# pcb_aux_sensors.net
KiCad netlist of a schematic drawn in EAGLE
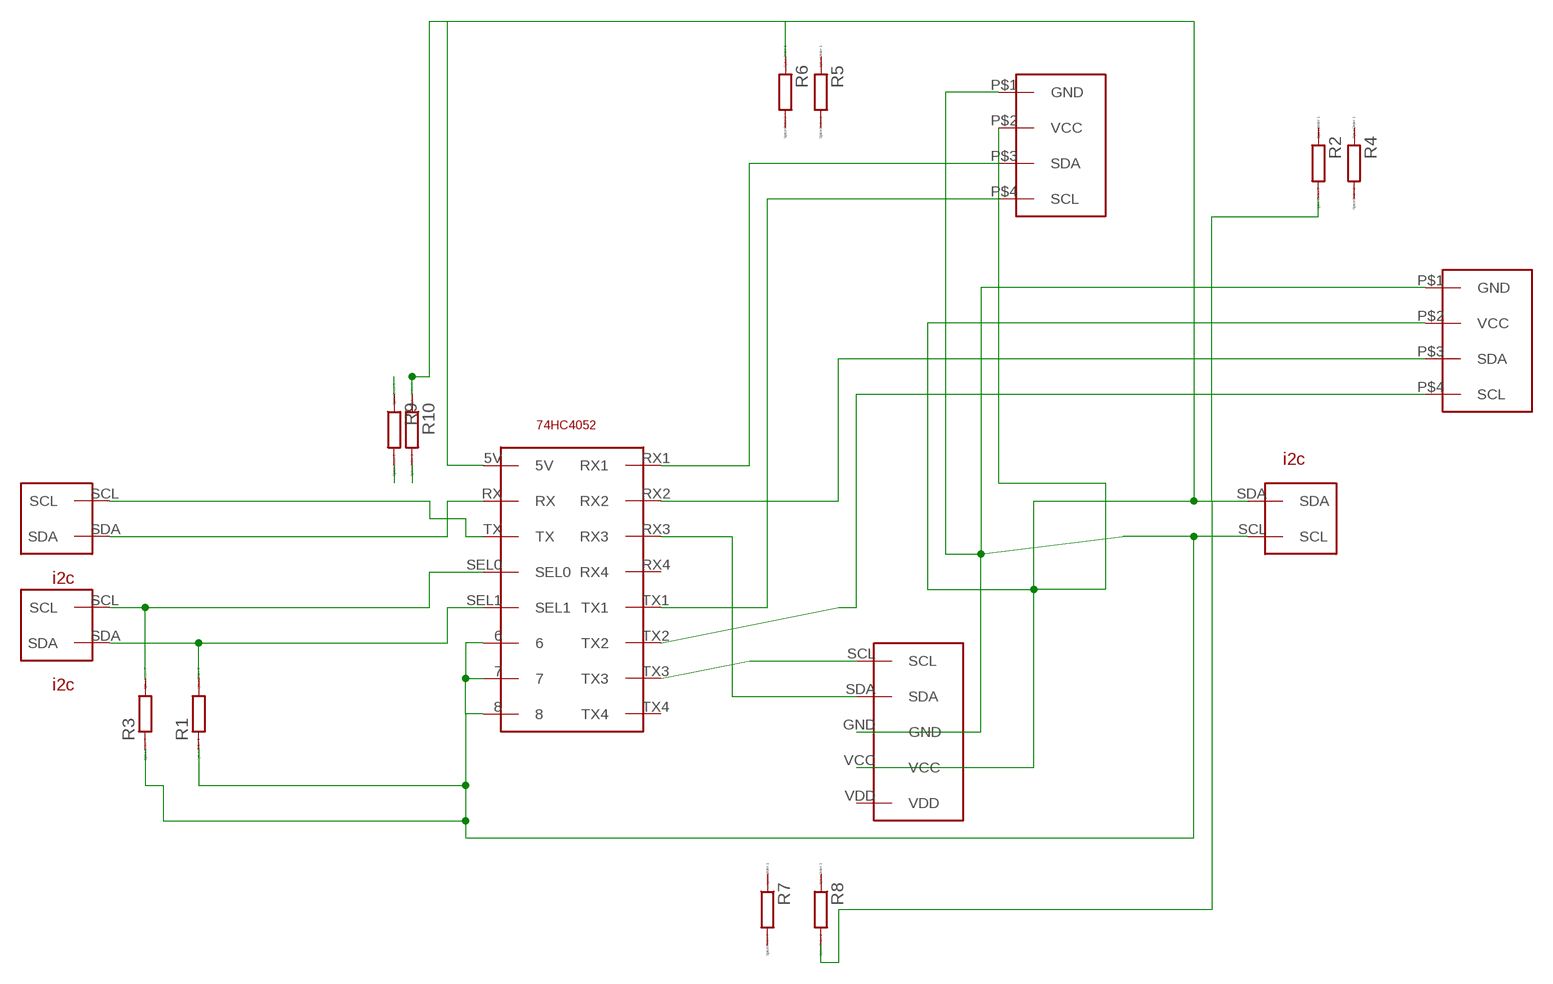
[diagram p0: schematic, sheet 1]

(export (version "E")
  (design (tool "Eeschema 10.0.6"))
  (components
    (comp (ref "I2C")
      (value "I2C")
      (footprint "eagle-import:I2C")
      (libsource (lib "eagle-import") (part "I2C"))
    )
    (comp (ref "MUXSELECT")
      (value "I2C")
      (footprint "eagle-import:I2C")
      (libsource (lib "eagle-import") (part "I2C"))
    )
    (comp (ref "PWR")
      (value "I2C")
      (footprint "eagle-import:I2C")
      (libsource (lib "eagle-import") (part "I2C"))
    )
    (comp (ref "R1")
      (value "R0204/7")
      (footprint "eagle-import:0204_7")
      (libsource (lib "eagle-import") (part "R0204/7"))
    )
    (comp (ref "R2")
      (value "R0204/7")
      (footprint "eagle-import:0204_7")
      (libsource (lib "eagle-import") (part "R0204/7"))
    )
    (comp (ref "R3")
      (value "R0204/7")
      (footprint "eagle-import:0204_7")
      (libsource (lib "eagle-import") (part "R0204/7"))
    )
    (comp (ref "R4")
      (value "R0204/7")
      (footprint "eagle-import:0204_7")
      (libsource (lib "eagle-import") (part "R0204/7"))
    )
    (comp (ref "R5")
      (value "R0204/7")
      (footprint "eagle-import:0204_7")
      (libsource (lib "eagle-import") (part "R0204/7"))
    )
    (comp (ref "R6")
      (value "R0204/7")
      (footprint "eagle-import:0204_7")
      (libsource (lib "eagle-import") (part "R0204/7"))
    )
    (comp (ref "R7")
      (value "R0204/7")
      (footprint "eagle-import:0204_7")
      (libsource (lib "eagle-import") (part "R0204/7"))
    )
    (comp (ref "R8")
      (value "R0204/7")
      (footprint "eagle-import:0204_7")
      (libsource (lib "eagle-import") (part "R0204/7"))
    )
    (comp (ref "R9")
      (value "R0204/7")
      (footprint "eagle-import:0204_7")
      (libsource (lib "eagle-import") (part "R0204/7"))
    )
    (comp (ref "R10")
      (value "R0204/7")
      (footprint "eagle-import:0204_7")
      (libsource (lib "eagle-import") (part "R0204/7"))
    )
    (comp (ref "U$2")
      (value "74HC4052")
      (footprint "eagle-import:74HC4052")
      (libsource (lib "eagle-import") (part "74HC4052"))
    )
    (comp (ref "U$5")
      (value "GROVECOLORSENSOR")
      (footprint "eagle-import:GROVECOLORSENSOR")
      (libsource (lib "eagle-import") (part "GROVECOLORSENSOR"))
    )
    (comp (ref "U$6")
      (value "GROVECOLORSENSOR")
      (footprint "eagle-import:GROVECOLORSENSOR")
      (libsource (lib "eagle-import") (part "GROVECOLORSENSOR"))
    )
    (comp (ref "U$7")
      (value "MINIMU9_V4")
      (footprint "eagle-import:MINIMU9_V4")
      (libsource (lib "eagle-import") (part "MINIMU9_V4"))
    )
  )
  (nets
    (net (code "1") (name "Net-(I2C-PadSCL)") (class "Default")
      (node (ref "I2C") (pin "SCL") (pinfunction "SCL_SCL") (pintype "bidirectional"))
      (node (ref "U$2") (pin "TX") (pinfunction "TX_TX") (pintype "bidirectional"))
    )
    (net (code "2") (name "Net-(I2C-PadSDA)") (class "Default")
      (node (ref "I2C") (pin "SDA") (pinfunction "SDA_SDA") (pintype "bidirectional"))
      (node (ref "U$2") (pin "RX") (pinfunction "RX_RX") (pintype "bidirectional"))
    )
    (net (code "3") (name "Net-(MUXSELECT-PadSCL)") (class "Default")
      (node (ref "MUXSELECT") (pin "SCL") (pinfunction "SCL_SCL") (pintype "bidirectional"))
      (node (ref "R3") (pin "2") (pinfunction "2_2") (pintype "passive"))
      (node (ref "U$2") (pin "SEL0") (pinfunction "SEL0_SEL0") (pintype "bidirectional"))
    )
    (net (code "4") (name "Net-(MUXSELECT-PadSDA)") (class "Default")
      (node (ref "MUXSELECT") (pin "SDA") (pinfunction "SDA_SDA") (pintype "bidirectional"))
      (node (ref "R1") (pin "2") (pinfunction "2_2") (pintype "passive"))
      (node (ref "U$2") (pin "SEL1") (pinfunction "SEL1_SEL1") (pintype "bidirectional"))
    )
    (net (code "5") (name "Net-(U$2-PadRX3)") (class "Default")
      (node (ref "U$2") (pin "RX3") (pinfunction "RX3_RX3") (pintype "bidirectional"))
      (node (ref "U$7") (pin "SDA") (pinfunction "SDA_SDA") (pintype "bidirectional"))
    )
    (net (code "6") (name "Net-(U$2-PadTX3)") (class "Default")
      (node (ref "U$2") (pin "TX3") (pinfunction "TX3_TX3") (pintype "bidirectional"))
      (node (ref "U$7") (pin "SCL") (pinfunction "SCL_SCL") (pintype "bidirectional"))
    )
    (net (code "7") (name "Net-(U$5-GND)") (class "Default")
      (node (ref "PWR") (pin "SCL") (pinfunction "SCL_SCL") (pintype "bidirectional"))
      (node (ref "R1") (pin "1") (pinfunction "1_1") (pintype "passive"))
      (node (ref "R3") (pin "1") (pinfunction "1_1") (pintype "passive"))
      (node (ref "U$2") (pin "6") (pinfunction "6_6") (pintype "bidirectional"))
      (node (ref "U$2") (pin "7") (pinfunction "7_7") (pintype "bidirectional"))
      (node (ref "U$2") (pin "8") (pinfunction "8_8") (pintype "bidirectional"))
      (node (ref "U$5") (pin "P$1") (pinfunction "GND_P$1") (pintype "bidirectional"))
      (node (ref "U$6") (pin "P$1") (pinfunction "GND_P$1") (pintype "bidirectional"))
      (node (ref "U$7") (pin "GND") (pinfunction "GND_GND") (pintype "bidirectional"))
    )
    (net (code "8") (name "Net-(U$5-SCL)") (class "Default")
      (node (ref "U$2") (pin "TX1") (pinfunction "TX1_TX1") (pintype "bidirectional"))
      (node (ref "U$5") (pin "P$4") (pinfunction "SCL_P$4") (pintype "bidirectional"))
    )
    (net (code "9") (name "Net-(U$5-SDA)") (class "Default")
      (node (ref "U$2") (pin "RX1") (pinfunction "RX1_RX1") (pintype "bidirectional"))
      (node (ref "U$5") (pin "P$3") (pinfunction "SDA_P$3") (pintype "bidirectional"))
    )
    (net (code "10") (name "Net-(U$5-VCC)") (class "Default")
      (node (ref "PWR") (pin "SDA") (pinfunction "SDA_SDA") (pintype "bidirectional"))
      (node (ref "R10") (pin "1") (pinfunction "1_1") (pintype "passive"))
      (node (ref "R2") (pin "2") (pinfunction "2_2") (pintype "passive"))
      (node (ref "R6") (pin "1") (pinfunction "1_1") (pintype "passive"))
      (node (ref "R8") (pin "2") (pinfunction "2_2") (pintype "passive"))
      (node (ref "U$2") (pin "5V") (pinfunction "5V_5V") (pintype "bidirectional"))
      (node (ref "U$5") (pin "P$2") (pinfunction "VCC_P$2") (pintype "bidirectional"))
      (node (ref "U$6") (pin "P$2") (pinfunction "VCC_P$2") (pintype "bidirectional"))
      (node (ref "U$7") (pin "VCC") (pinfunction "VCC_VCC") (pintype "bidirectional"))
    )
    (net (code "11") (name "Net-(U$6-SCL)") (class "Default")
      (node (ref "U$2") (pin "TX2") (pinfunction "TX2_TX2") (pintype "bidirectional"))
      (node (ref "U$6") (pin "P$4") (pinfunction "SCL_P$4") (pintype "bidirectional"))
    )
    (net (code "12") (name "Net-(U$6-SDA)") (class "Default")
      (node (ref "U$2") (pin "RX2") (pinfunction "RX2_RX2") (pintype "bidirectional"))
      (node (ref "U$6") (pin "P$3") (pinfunction "SDA_P$3") (pintype "bidirectional"))
    )
    (net (code "13") (name "unconnected-(R2-Pad1)") (class "Default")
      (node (ref "R2") (pin "1") (pinfunction "1_1") (pintype "passive"))
    )
    (net (code "14") (name "unconnected-(R4-Pad1)") (class "Default")
      (node (ref "R4") (pin "1") (pinfunction "1_1") (pintype "passive"))
    )
    (net (code "15") (name "unconnected-(R4-Pad2)") (class "Default")
      (node (ref "R4") (pin "2") (pinfunction "2_2") (pintype "passive"))
    )
    (net (code "16") (name "unconnected-(R5-Pad1)") (class "Default")
      (node (ref "R5") (pin "1") (pinfunction "1_1") (pintype "passive"))
    )
    (net (code "17") (name "unconnected-(R5-Pad2)") (class "Default")
      (node (ref "R5") (pin "2") (pinfunction "2_2") (pintype "passive"))
    )
    (net (code "18") (name "unconnected-(R6-Pad2)") (class "Default")
      (node (ref "R6") (pin "2") (pinfunction "2_2") (pintype "passive"))
    )
    (net (code "19") (name "unconnected-(R7-Pad1)") (class "Default")
      (node (ref "R7") (pin "1") (pinfunction "1_1") (pintype "passive"))
    )
    (net (code "20") (name "unconnected-(R7-Pad2)") (class "Default")
      (node (ref "R7") (pin "2") (pinfunction "2_2") (pintype "passive"))
    )
    (net (code "21") (name "unconnected-(R8-Pad1)") (class "Default")
      (node (ref "R8") (pin "1") (pinfunction "1_1") (pintype "passive"))
    )
    (net (code "22") (name "unconnected-(R9-Pad1)") (class "Default")
      (node (ref "R9") (pin "1") (pinfunction "1_1") (pintype "passive"))
    )
    (net (code "23") (name "unconnected-(R9-Pad2)") (class "Default")
      (node (ref "R9") (pin "2") (pinfunction "2_2") (pintype "passive"))
    )
    (net (code "24") (name "unconnected-(R10-Pad2)") (class "Default")
      (node (ref "R10") (pin "2") (pinfunction "2_2") (pintype "passive"))
    )
    (net (code "25") (name "unconnected-(U$2-PadRX4)") (class "Default")
      (node (ref "U$2") (pin "RX4") (pinfunction "RX4_RX4") (pintype "bidirectional"))
    )
    (net (code "26") (name "unconnected-(U$2-PadTX4)") (class "Default")
      (node (ref "U$2") (pin "TX4") (pinfunction "TX4_TX4") (pintype "bidirectional"))
    )
    (net (code "27") (name "unconnected-(U$7-PadVDD)") (class "Default")
      (node (ref "U$7") (pin "VDD") (pinfunction "VDD_VDD") (pintype "bidirectional"))
    )
  )
)
